# 01_-_MC.net
KiCad netlist of a schematic drawn in Altium Designer
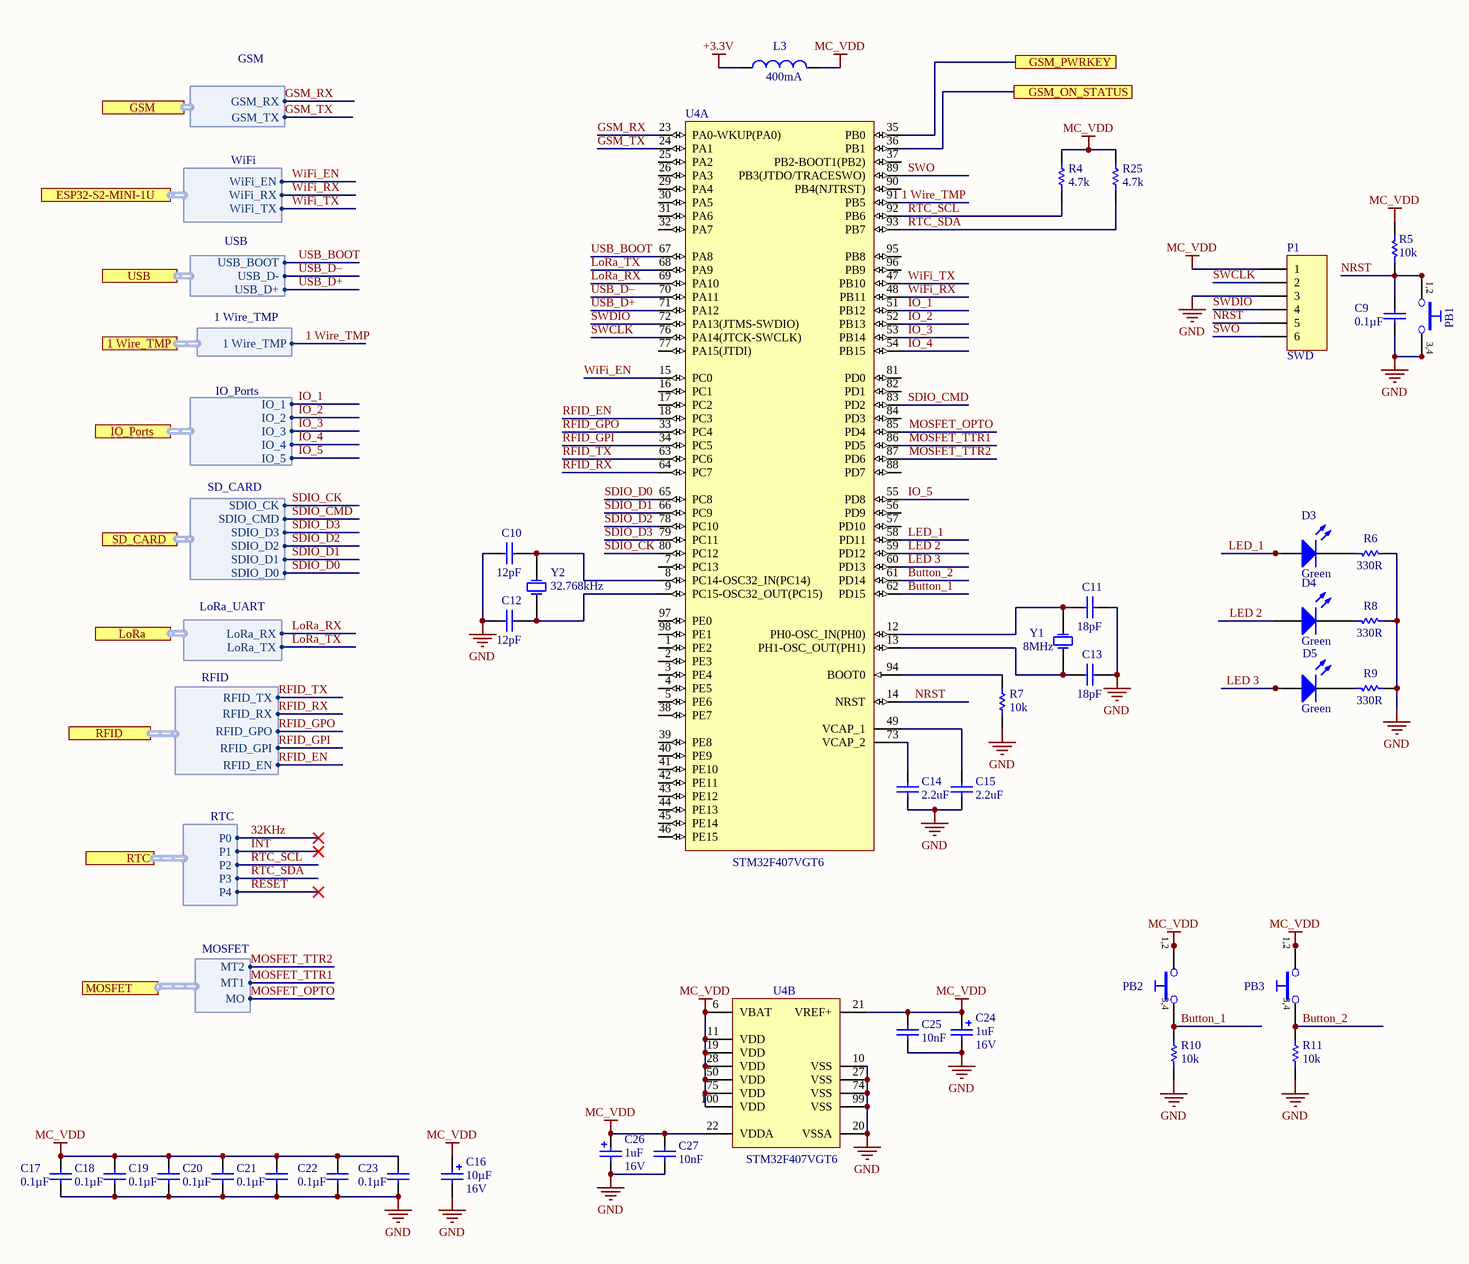
[diagram p0: [01] - MC.SchDoc]

(export (version "E")
  (design (tool "Eeschema 10.0.6"))
  (components
    (comp (ref "C9")
      (value "Capacitor")
      (footprint "Cap 0603")
      (description "Chip Capacitor Nonpolar")
      (fields
        (field (name "MANUFACTURER") "Kemet")
        (field (name "MANUFACTURER PART NUMBER") "C0603C104K5RACTU")
        (field (name "CAPACITANCE") "0.1µF")
      )
      (libsource (lib "Altium_Library") (part "Capacitor"))
    )
    (comp (ref "C10")
      (value "Capacitor")
      (footprint "Cap 0603")
      (description "Chip Capacitor Nonpolar")
      (fields
        (field (name "MANUFACTURER") "KEMET")
        (field (name "MANUFACTURER PART NUMBER") "C0603C120J5GAC-TU")
        (field (name "CAPACITANCE") "12pF")
      )
      (libsource (lib "Altium_Library") (part "Capacitor"))
    )
    (comp (ref "C11")
      (value "Capacitor")
      (footprint "Cap 0603")
      (description "Chip Capacitor Nonpolar")
      (fields
        (field (name "MANUFACTURER") "KEMET")
        (field (name "MANUFACTURER PART NUMBER") "C0603C180K5GACTU")
        (field (name "CAPACITANCE") "18pF")
      )
      (libsource (lib "Altium_Library") (part "Capacitor"))
    )
    (comp (ref "C12")
      (value "Capacitor")
      (footprint "Cap 0603")
      (description "Chip Capacitor Nonpolar")
      (fields
        (field (name "MANUFACTURER") "KEMET")
        (field (name "MANUFACTURER PART NUMBER") "C0603C120J5GAC-TU")
        (field (name "CAPACITANCE") "12pF")
      )
      (libsource (lib "Altium_Library") (part "Capacitor"))
    )
    (comp (ref "C13")
      (value "Capacitor")
      (footprint "Cap 0603")
      (description "Chip Capacitor Nonpolar")
      (fields
        (field (name "MANUFACTURER") "KEMET")
        (field (name "MANUFACTURER PART NUMBER") "C0603C180K5GACTU")
        (field (name "CAPACITANCE") "18pF")
      )
      (libsource (lib "Altium_Library") (part "Capacitor"))
    )
    (comp (ref "C14")
      (value "Capacitor")
      (footprint "Cap 0603")
      (description "Chip Capacitor Nonpolar")
      (fields
        (field (name "MANUFACTURER") "Samsung")
        (field (name "MANUFACTURER PART NUMBER") "CL21A225KAFNNNG")
        (field (name "CAPACITANCE") "2.2uF")
      )
      (libsource (lib "Altium_Library") (part "Capacitor"))
    )
    (comp (ref "C15")
      (value "Capacitor")
      (footprint "Cap 0603")
      (description "Chip Capacitor Nonpolar")
      (fields
        (field (name "MANUFACTURER") "Samsung")
        (field (name "MANUFACTURER PART NUMBER") "CL21A225KAFNNNG")
        (field (name "CAPACITANCE") "2.2uF")
      )
      (libsource (lib "Altium_Library") (part "Capacitor"))
    )
    (comp (ref "C16")
      (value "Capacitor Polarized")
      (footprint "Tantalum 3216 A")
      (description "Tantalum Capacitor")
      (fields
        (field (name "MANUFACTURER") "Kemet")
        (field (name "MANUFACTURER PART NUMBER") "T491A106K016AT")
        (field (name "CAPACITANCE") "10µF")
        (field (name "VOLTAGE - RATED") "16V")
      )
      (libsource (lib "Altium_Library") (part "Capacitor Polarized"))
    )
    (comp (ref "C17")
      (value "Capacitor")
      (footprint "Cap 0603")
      (description "Chip Capacitor Nonpolar")
      (fields
        (field (name "MANUFACTURER") "Kemet")
        (field (name "MANUFACTURER PART NUMBER") "C0603C104K5RACTU")
        (field (name "CAPACITANCE") "0.1µF")
      )
      (libsource (lib "Altium_Library") (part "Capacitor"))
    )
    (comp (ref "C18")
      (value "Capacitor")
      (footprint "Cap 0603")
      (description "Chip Capacitor Nonpolar")
      (fields
        (field (name "MANUFACTURER") "Kemet")
        (field (name "MANUFACTURER PART NUMBER") "C0603C104K5RACTU")
        (field (name "CAPACITANCE") "0.1µF")
      )
      (libsource (lib "Altium_Library") (part "Capacitor"))
    )
    (comp (ref "C19")
      (value "Capacitor")
      (footprint "Cap 0603")
      (description "Chip Capacitor Nonpolar")
      (fields
        (field (name "MANUFACTURER") "Kemet")
        (field (name "MANUFACTURER PART NUMBER") "C0603C104K5RACTU")
        (field (name "CAPACITANCE") "0.1µF")
      )
      (libsource (lib "Altium_Library") (part "Capacitor"))
    )
    (comp (ref "C20")
      (value "Capacitor")
      (footprint "Cap 0603")
      (description "Chip Capacitor Nonpolar")
      (fields
        (field (name "MANUFACTURER") "Kemet")
        (field (name "MANUFACTURER PART NUMBER") "C0603C104K5RACTU")
        (field (name "CAPACITANCE") "0.1µF")
      )
      (libsource (lib "Altium_Library") (part "Capacitor"))
    )
    (comp (ref "C21")
      (value "Capacitor")
      (footprint "Cap 0603")
      (description "Chip Capacitor Nonpolar")
      (fields
        (field (name "MANUFACTURER") "Kemet")
        (field (name "MANUFACTURER PART NUMBER") "C0603C104K5RACTU")
        (field (name "CAPACITANCE") "0.1µF")
      )
      (libsource (lib "Altium_Library") (part "Capacitor"))
    )
    (comp (ref "C22")
      (value "Capacitor")
      (footprint "Cap 0603")
      (description "Chip Capacitor Nonpolar")
      (fields
        (field (name "MANUFACTURER") "Kemet")
        (field (name "MANUFACTURER PART NUMBER") "C0603C104K5RACTU")
        (field (name "CAPACITANCE") "0.1µF")
      )
      (libsource (lib "Altium_Library") (part "Capacitor"))
    )
    (comp (ref "C23")
      (value "Capacitor")
      (footprint "Cap 0603")
      (description "Chip Capacitor Nonpolar")
      (fields
        (field (name "MANUFACTURER") "Kemet")
        (field (name "MANUFACTURER PART NUMBER") "C0603C104K5RACTU")
        (field (name "CAPACITANCE") "0.1µF")
      )
      (libsource (lib "Altium_Library") (part "Capacitor"))
    )
    (comp (ref "C24")
      (value "Capacitor Polarized")
      (footprint "Tantalum 3216 A")
      (description "Tantalum Capacitor")
      (fields
        (field (name "MANUFACTURER") "Vishay Sprague")
        (field (name "MANUFACTURER PART NUMBER") "293D105X9016A2TE3")
        (field (name "CAPACITANCE") "1uF")
        (field (name "VOLTAGE RATING") "16V")
      )
      (libsource (lib "Altium_Library") (part "Capacitor Polarized"))
    )
    (comp (ref "C25")
      (value "Capacitor")
      (footprint "Cap 0603")
      (description "Chip Capacitor Nonpolar")
      (fields
        (field (name "MANUFACTURER") "Samsung")
        (field (name "MANUFACTURER PART NUMBER") "CL10B103KB8WPNC")
        (field (name "CAPACITANCE") "10nF")
      )
      (libsource (lib "Altium_Library") (part "Capacitor"))
    )
    (comp (ref "C26")
      (value "Capacitor Polarized")
      (footprint "Tantalum 3216 A")
      (description "Tantalum Capacitor")
      (fields
        (field (name "MANUFACTURER") "Vishay Sprague")
        (field (name "MANUFACTURER PART NUMBER") "293D105X9016A2TE3")
        (field (name "CAPACITANCE") "1uF")
        (field (name "VOLTAGE RATING") "16V")
      )
      (libsource (lib "Altium_Library") (part "Capacitor Polarized"))
    )
    (comp (ref "C27")
      (value "Capacitor")
      (footprint "Cap 0603")
      (description "Chip Capacitor Nonpolar")
      (fields
        (field (name "MANUFACTURER") "Samsung")
        (field (name "MANUFACTURER PART NUMBER") "CL10B103KB8WPNC")
        (field (name "CAPACITANCE") "10nF")
      )
      (libsource (lib "Altium_Library") (part "Capacitor"))
    )
    (comp (ref "D3")
      (value "LED")
      (footprint "Led 0805 green")
      (description "Led 0805")
      (fields
        (field (name "MANUFACTURER") "Vishay Lite-On")
        (field (name "MANUFACTURER PART NUMBER") "LTST-S220GKT")
        (field (name "COLOUR") "Green")
      )
      (libsource (lib "Altium_Library") (part "LED"))
    )
    (comp (ref "D4")
      (value "LED")
      (footprint "Led 0805 green")
      (description "Led 0805")
      (fields
        (field (name "MANUFACTURER") "Vishay Lite-On")
        (field (name "MANUFACTURER PART NUMBER") "LTST-S220GKT")
        (field (name "COLOUR") "Green")
      )
      (libsource (lib "Altium_Library") (part "LED"))
    )
    (comp (ref "D5")
      (value "LED")
      (footprint "Led 0805 green")
      (description "Led 0805")
      (fields
        (field (name "MANUFACTURER") "Vishay Lite-On")
        (field (name "MANUFACTURER PART NUMBER") "LTST-S220GKT")
        (field (name "COLOUR") "Green")
      )
      (libsource (lib "Altium_Library") (part "LED"))
    )
    (comp (ref "L3")
      (value "Inductor")
      (footprint "0603")
      (description "Sumida inductore ferrite core smd")
      (fields
        (field (name "MANUFACTURER") "Murata Electronics North America")
        (field (name "MANUFACTURER PART NUMBER") "BLM18AG102SN1D")
        (field (name "CURRENT RATING (MAX)") "400mA")
      )
      (libsource (lib "Altium_Library") (part "Inductor"))
    )
    (comp (ref "P1")
      (value "SWD")
      (footprint "HDR1X6")
      (description "Header, 6-Pin")
      (fields (field (name "PUBLISHER") "Altium Limited"))
      (libsource (lib "Miscellaneous Connectors") (part "Header 6"))
    )
    (comp (ref "PB1")
      (value "Push Button")
      (footprint "PB_OMRON_B3F-1000")
      (description "Push-Button Switch SPDT")
      (fields
        (field (name "PART NUMBER") "PB_OMRON_B3F-1000")
        (field (name "MANUFACTURER") "OMRON")
        (field (name "AUTHOR") "CERN DEM JMW")
      )
      (libsource (lib "") (part "PB SPST 12NO-34NO_1"))
    )
    (comp (ref "PB2")
      (value "Push Button")
      (footprint "PB_OMRON_B3F-1000")
      (description "Push-Button Switch SPDT")
      (fields
        (field (name "PART NUMBER") "PB_OMRON_B3F-1000")
        (field (name "MANUFACTURER") "OMRON")
        (field (name "AUTHOR") "CERN DEM JMW")
      )
      (libsource (lib "Eletro-mechanical") (part "PB SPST 12NO-34NO"))
    )
    (comp (ref "PB3")
      (value "Push Button")
      (footprint "PB_OMRON_B3F-1000")
      (description "Push-Button Switch SPDT")
      (fields
        (field (name "PART NUMBER") "PB_OMRON_B3F-1000")
        (field (name "MANUFACTURER") "OMRON")
        (field (name "AUTHOR") "CERN DEM JMW")
      )
      (libsource (lib "Eletro-mechanical") (part "PB SPST 12NO-34NO"))
    )
    (comp (ref "R4")
      (value "Res1")
      (footprint "Res-0603")
      (description "Chip Resistor")
      (fields
        (field (name "MANUFACTURER") "Panasonic")
        (field (name "MANUFACTURER PART NUMBER") "ERJ-3GEYJ222V")
        (field (name "RESISTANCE") "4.7k")
      )
      (libsource (lib "Altium_Library") (part "Res1"))
    )
    (comp (ref "R5")
      (value "Res1")
      (footprint "Res-0603")
      (description "Chip Resistor")
      (fields
        (field (name "MANUFACTURER") "Panasonic")
        (field (name "MANUFACTURER PART NUMBER") "ERJ-3GEYJ103V")
        (field (name "RESISTANCE") "10k")
      )
      (libsource (lib "Altium_Library") (part "Res1"))
    )
    (comp (ref "R6")
      (value "Res1")
      (footprint "Res-0603")
      (description "Chip Resistor")
      (fields
        (field (name "MANUFACTURER") "Panasonic")
        (field (name "MANUFACTURER PART NUMBER") "ERJ-3EKF3300V")
        (field (name "RESISTANCE") "330R")
      )
      (libsource (lib "Altium_Library") (part "Res1"))
    )
    (comp (ref "R7")
      (value "Res1")
      (footprint "Res-0603")
      (description "Chip Resistor")
      (fields
        (field (name "MANUFACTURER") "Panasonic")
        (field (name "MANUFACTURER PART NUMBER") "ERJ-3GEYJ103V")
        (field (name "RESISTANCE") "10k")
      )
      (libsource (lib "Altium_Library") (part "Res1"))
    )
    (comp (ref "R8")
      (value "Res1")
      (footprint "Res-0603")
      (description "Chip Resistor")
      (fields
        (field (name "MANUFACTURER") "Panasonic")
        (field (name "MANUFACTURER PART NUMBER") "ERJ-3EKF3300V")
        (field (name "RESISTANCE") "330R")
      )
      (libsource (lib "Altium_Library") (part "Res1"))
    )
    (comp (ref "R9")
      (value "Res1")
      (footprint "Res-0603")
      (description "Chip Resistor")
      (fields
        (field (name "MANUFACTURER") "Panasonic")
        (field (name "MANUFACTURER PART NUMBER") "ERJ-3EKF3300V")
        (field (name "RESISTANCE") "330R")
      )
      (libsource (lib "Altium_Library") (part "Res1"))
    )
    (comp (ref "R10")
      (value "Res1")
      (footprint "Res-0603")
      (description "Chip Resistor")
      (fields
        (field (name "MANUFACTURER") "Panasonic")
        (field (name "MANUFACTURER PART NUMBER") "ERJ-3GEYJ103V")
        (field (name "RESISTANCE") "10k")
      )
      (libsource (lib "Altium_Library") (part "Res1"))
    )
    (comp (ref "R11")
      (value "Res1")
      (footprint "Res-0603")
      (description "Chip Resistor")
      (fields
        (field (name "MANUFACTURER") "Panasonic")
        (field (name "MANUFACTURER PART NUMBER") "ERJ-3GEYJ103V")
        (field (name "RESISTANCE") "10k")
      )
      (libsource (lib "Altium_Library") (part "Res1"))
    )
    (comp (ref "R25")
      (value "Res1")
      (footprint "Res-0603")
      (description "Chip Resistor")
      (fields
        (field (name "MANUFACTURER") "Panasonic")
        (field (name "MANUFACTURER PART NUMBER") "ERJ-3GEYJ222V")
        (field (name "RESISTANCE") "4.7k")
      )
      (libsource (lib "Altium_Library") (part "Res1"))
    )
    (comp (ref "U4")
      (value "STM32F407VGT6J")
      (footprint "LQFP100_N")
      (fields
        (field (name "MANUFACTURER") "STMicroelectronics")
        (field (name "MANUFACTURER PART NUMBER") "STM32F407VGT6")
      )
      (libsource (lib "STMicroelectronics STM32 F4") (part "STM32F407VGT6J"))
    )
    (comp (ref "Y1")
      (value "XTAL2pin")
      (footprint "ABM3")
      (description "Crystal Oscillator")
      (fields
        (field (name "MANUFACTURER") "Abracon Corporation")
        (field (name "MANUFACTURER PART NUMBER") "ABM3-8.000MHZ-D2Y-T")
        (field (name "FREQUENCY") "8MHz")
        (field (name "PUBLISHER") "Ruslan Gimazetdinov")
      )
      (libsource (lib "Altium_Library") (part "XTAL2pin"))
    )
    (comp (ref "Y2")
      (value "32768")
      (footprint "ABM3")
      (description "Crystal Oscillator")
      (fields
        (field (name "MANUFACTURER") "ECS International")
        (field (name "MANUFACTURER PART NUMBER") "ECS-.327-12.5-34B-TR")
        (field (name "FREQUENCY") "32.768kHz")
      )
      (libsource (lib "Altium_Library") (part "XTAL2pin"))
    )
  )
  (nets
    (net (code "12") (name "+3.3V") (class "Default")
      (node (ref "L3") (pin "1") (pinfunction "1_1") (pintype "passive"))
    )
    (net (code "13") (name "/1 Wire_TMP") (class "Default")
      (node (ref "U4") (pin "91") (pinfunction "PB5_91") (pintype "bidirectional"))
    )
    (net (code "15") (name "/Button_1") (class "Default")
      (node (ref "PB2") (pin "3") (pinfunction "3_3") (pintype "passive"))
      (node (ref "PB2") (pin "4") (pinfunction "4_4") (pintype "passive"))
      (node (ref "R10") (pin "2") (pinfunction "2_2") (pintype "passive"))
      (node (ref "U4") (pin "62") (pinfunction "PD15_62") (pintype "bidirectional"))
    )
    (net (code "16") (name "/Button_2") (class "Default")
      (node (ref "PB3") (pin "3") (pinfunction "3_3") (pintype "passive"))
      (node (ref "PB3") (pin "4") (pinfunction "4_4") (pintype "passive"))
      (node (ref "R11") (pin "2") (pinfunction "2_2") (pintype "passive"))
      (node (ref "U4") (pin "61") (pinfunction "PD14_61") (pintype "bidirectional"))
    )
    (net (code "17") (name "/GSM_ON_STATUS") (class "Default")
      (node (ref "U4") (pin "36") (pinfunction "PB1_36") (pintype "bidirectional"))
    )
    (net (code "18") (name "/GSM_PWRKEY") (class "Default")
      (node (ref "U4") (pin "35") (pinfunction "PB0_35") (pintype "bidirectional"))
    )
    (net (code "19") (name "/GSM_RX") (class "Default")
      (node (ref "U4") (pin "23") (pinfunction "PA0-WKUP(PA0)_23") (pintype "bidirectional"))
    )
    (net (code "20") (name "/GSM_TX") (class "Default")
      (node (ref "U4") (pin "24") (pinfunction "PA1_24") (pintype "bidirectional"))
    )
    (net (code "21") (name "/IO_1") (class "Default")
      (node (ref "U4") (pin "51") (pinfunction "PB12_51") (pintype "bidirectional"))
    )
    (net (code "22") (name "/IO_2") (class "Default")
      (node (ref "U4") (pin "52") (pinfunction "PB13_52") (pintype "bidirectional"))
    )
    (net (code "23") (name "/IO_3") (class "Default")
      (node (ref "U4") (pin "53") (pinfunction "PB14_53") (pintype "bidirectional"))
    )
    (net (code "24") (name "/IO_4") (class "Default")
      (node (ref "U4") (pin "54") (pinfunction "PB15_54") (pintype "bidirectional"))
    )
    (net (code "25") (name "/IO_5") (class "Default")
      (node (ref "U4") (pin "55") (pinfunction "PD8_55") (pintype "bidirectional"))
    )
    (net (code "26") (name "/LED 2") (class "Default")
      (node (ref "D4") (pin "1") (pinfunction "A_1") (pintype "passive"))
      (node (ref "U4") (pin "59") (pinfunction "PD12_59") (pintype "bidirectional"))
    )
    (net (code "27") (name "/LED 3") (class "Default")
      (node (ref "D5") (pin "1") (pinfunction "A_1") (pintype "passive"))
      (node (ref "U4") (pin "60") (pinfunction "PD13_60") (pintype "bidirectional"))
    )
    (net (code "28") (name "/LED_1") (class "Default")
      (node (ref "D3") (pin "1") (pinfunction "A_1") (pintype "passive"))
      (node (ref "U4") (pin "58") (pinfunction "PD11_58") (pintype "bidirectional"))
    )
    (net (code "29") (name "/LoRa_RX") (class "Default")
      (node (ref "U4") (pin "69") (pinfunction "PA10_69") (pintype "bidirectional"))
    )
    (net (code "30") (name "/LoRa_TX") (class "Default")
      (node (ref "U4") (pin "68") (pinfunction "PA9_68") (pintype "bidirectional"))
    )
    (net (code "31") (name "/MOSFET_OPTO") (class "Default")
      (node (ref "U4") (pin "85") (pinfunction "PD4_85") (pintype "bidirectional"))
    )
    (net (code "32") (name "/MOSFET_TTR1") (class "Default")
      (node (ref "U4") (pin "86") (pinfunction "PD5_86") (pintype "bidirectional"))
    )
    (net (code "33") (name "/MOSFET_TTR2") (class "Default")
      (node (ref "U4") (pin "87") (pinfunction "PD6_87") (pintype "bidirectional"))
    )
    (net (code "34") (name "/NRST") (class "Default")
      (node (ref "C9") (pin "2") (pinfunction "2_2") (pintype "passive"))
      (node (ref "P1") (pin "5") (pinfunction "5_5") (pintype "passive"))
      (node (ref "PB1") (pin "1") (pinfunction "1_1") (pintype "passive"))
      (node (ref "PB1") (pin "2") (pinfunction "2_2") (pintype "passive"))
      (node (ref "R5") (pin "1") (pinfunction "1_1") (pintype "passive"))
      (node (ref "U4") (pin "14") (pinfunction "NRST_14") (pintype "bidirectional"))
    )
    (net (code "36") (name "/RFID_EN") (class "Default")
      (node (ref "U4") (pin "18") (pinfunction "PC3_18") (pintype "bidirectional"))
    )
    (net (code "37") (name "/RFID_GPI") (class "Default")
      (node (ref "U4") (pin "34") (pinfunction "PC5_34") (pintype "bidirectional"))
    )
    (net (code "38") (name "/RFID_GPO") (class "Default")
      (node (ref "U4") (pin "33") (pinfunction "PC4_33") (pintype "bidirectional"))
    )
    (net (code "39") (name "/RFID_RX") (class "Default")
      (node (ref "U4") (pin "64") (pinfunction "PC7_64") (pintype "bidirectional"))
    )
    (net (code "40") (name "/RFID_TX") (class "Default")
      (node (ref "U4") (pin "63") (pinfunction "PC6_63") (pintype "bidirectional"))
    )
    (net (code "41") (name "/RTC_SCL") (class "Default")
      (node (ref "R4") (pin "2") (pinfunction "2_2") (pintype "passive"))
      (node (ref "U4") (pin "92") (pinfunction "PB6_92") (pintype "bidirectional"))
    )
    (net (code "42") (name "/RTC_SDA") (class "Default")
      (node (ref "R25") (pin "2") (pinfunction "2_2") (pintype "passive"))
      (node (ref "U4") (pin "93") (pinfunction "PB7_93") (pintype "bidirectional"))
    )
    (net (code "43") (name "/SDIO_CK") (class "Default")
      (node (ref "U4") (pin "80") (pinfunction "PC12_80") (pintype "bidirectional"))
    )
    (net (code "44") (name "/SDIO_CMD") (class "Default")
      (node (ref "U4") (pin "83") (pinfunction "PD2_83") (pintype "bidirectional"))
    )
    (net (code "45") (name "/SDIO_D0") (class "Default")
      (node (ref "U4") (pin "65") (pinfunction "PC8_65") (pintype "bidirectional"))
    )
    (net (code "46") (name "/SDIO_D1") (class "Default")
      (node (ref "U4") (pin "66") (pinfunction "PC9_66") (pintype "bidirectional"))
    )
    (net (code "47") (name "/SDIO_D2") (class "Default")
      (node (ref "U4") (pin "78") (pinfunction "PC10_78") (pintype "bidirectional"))
    )
    (net (code "48") (name "/SDIO_D3") (class "Default")
      (node (ref "U4") (pin "79") (pinfunction "PC11_79") (pintype "bidirectional"))
    )
    (net (code "49") (name "/SWCLK") (class "Default")
      (node (ref "P1") (pin "2") (pinfunction "2_2") (pintype "passive"))
      (node (ref "U4") (pin "76") (pinfunction "PA14(JTCK-SWCLK)_76") (pintype "bidirectional"))
    )
    (net (code "50") (name "/SWDIO") (class "Default")
      (node (ref "P1") (pin "4") (pinfunction "4_4") (pintype "passive"))
      (node (ref "U4") (pin "72") (pinfunction "PA13(JTMS-SWDIO)_72") (pintype "bidirectional"))
    )
    (net (code "51") (name "/SWO") (class "Default")
      (node (ref "P1") (pin "6") (pinfunction "6_6") (pintype "passive"))
      (node (ref "U4") (pin "89") (pinfunction "PB3(JTDO/TRACESWO)_89") (pintype "bidirectional"))
    )
    (net (code "52") (name "/USB_BOOT") (class "Default")
      (node (ref "U4") (pin "67") (pinfunction "PA8_67") (pintype "bidirectional"))
    )
    (net (code "53") (name "/USB_D+") (class "Default")
      (node (ref "U4") (pin "71") (pinfunction "PA12_71") (pintype "bidirectional"))
    )
    (net (code "54") (name "/USB_D–") (class "Default")
      (node (ref "U4") (pin "70") (pinfunction "PA11_70") (pintype "bidirectional"))
    )
    (net (code "55") (name "/WiFi_EN") (class "Default")
      (node (ref "U4") (pin "15") (pinfunction "PC0_15") (pintype "bidirectional"))
    )
    (net (code "56") (name "/WiFi_RX") (class "Default")
      (node (ref "U4") (pin "48") (pinfunction "PB11_48") (pintype "bidirectional"))
    )
    (net (code "57") (name "/WiFi_TX") (class "Default")
      (node (ref "U4") (pin "47") (pinfunction "PB10_47") (pintype "bidirectional"))
    )
    (net (code "69") (name "GND") (class "Default")
      (node (ref "C10") (pin "2") (pinfunction "2_2") (pintype "passive"))
      (node (ref "C11") (pin "2") (pinfunction "2_2") (pintype "passive"))
      (node (ref "C12") (pin "2") (pinfunction "2_2") (pintype "passive"))
      (node (ref "C13") (pin "2") (pinfunction "2_2") (pintype "passive"))
      (node (ref "C14") (pin "1") (pinfunction "1_1") (pintype "passive"))
      (node (ref "C15") (pin "1") (pinfunction "1_1") (pintype "passive"))
      (node (ref "C16") (pin "2") (pinfunction "2_2") (pintype "passive"))
      (node (ref "C17") (pin "1") (pinfunction "1_1") (pintype "passive"))
      (node (ref "C18") (pin "1") (pinfunction "1_1") (pintype "passive"))
      (node (ref "C19") (pin "1") (pinfunction "1_1") (pintype "passive"))
      (node (ref "C20") (pin "1") (pinfunction "1_1") (pintype "passive"))
      (node (ref "C21") (pin "1") (pinfunction "1_1") (pintype "passive"))
      (node (ref "C22") (pin "1") (pinfunction "1_1") (pintype "passive"))
      (node (ref "C23") (pin "1") (pinfunction "1_1") (pintype "passive"))
      (node (ref "C24") (pin "2") (pinfunction "2_2") (pintype "passive"))
      (node (ref "C25") (pin "1") (pinfunction "1_1") (pintype "passive"))
      (node (ref "C26") (pin "2") (pinfunction "2_2") (pintype "passive"))
      (node (ref "C27") (pin "1") (pinfunction "1_1") (pintype "passive"))
      (node (ref "C9") (pin "1") (pinfunction "1_1") (pintype "passive"))
      (node (ref "P1") (pin "3") (pinfunction "3_3") (pintype "passive"))
      (node (ref "PB1") (pin "3") (pinfunction "3_3") (pintype "passive"))
      (node (ref "PB1") (pin "4") (pinfunction "4_4") (pintype "passive"))
      (node (ref "R10") (pin "1") (pinfunction "1_1") (pintype "passive"))
      (node (ref "R11") (pin "1") (pinfunction "1_1") (pintype "passive"))
      (node (ref "R6") (pin "2") (pinfunction "2_2") (pintype "passive"))
      (node (ref "R7") (pin "1") (pinfunction "1_1") (pintype "passive"))
      (node (ref "R8") (pin "2") (pinfunction "2_2") (pintype "passive"))
      (node (ref "R9") (pin "2") (pinfunction "2_2") (pintype "passive"))
      (node (ref "U4") (pin "10") (pinfunction "VSS_10") (pintype "power_in"))
      (node (ref "U4") (pin "20") (pinfunction "VSSA_20") (pintype "power_in"))
      (node (ref "U4") (pin "27") (pinfunction "VSS_27") (pintype "power_in"))
      (node (ref "U4") (pin "74") (pinfunction "VSS_74") (pintype "power_in"))
      (node (ref "U4") (pin "99") (pinfunction "VSS_99") (pintype "power_in"))
    )
    (net (code "70") (name "MC_VDD") (class "Default")
      (node (ref "C16") (pin "1") (pinfunction "1_1") (pintype "passive"))
      (node (ref "C17") (pin "2") (pinfunction "2_2") (pintype "passive"))
      (node (ref "C18") (pin "2") (pinfunction "2_2") (pintype "passive"))
      (node (ref "C19") (pin "2") (pinfunction "2_2") (pintype "passive"))
      (node (ref "C20") (pin "2") (pinfunction "2_2") (pintype "passive"))
      (node (ref "C21") (pin "2") (pinfunction "2_2") (pintype "passive"))
      (node (ref "C22") (pin "2") (pinfunction "2_2") (pintype "passive"))
      (node (ref "C23") (pin "2") (pinfunction "2_2") (pintype "passive"))
      (node (ref "C24") (pin "1") (pinfunction "1_1") (pintype "passive"))
      (node (ref "C25") (pin "2") (pinfunction "2_2") (pintype "passive"))
      (node (ref "C26") (pin "1") (pinfunction "1_1") (pintype "passive"))
      (node (ref "C27") (pin "2") (pinfunction "2_2") (pintype "passive"))
      (node (ref "L3") (pin "2") (pinfunction "2_2") (pintype "passive"))
      (node (ref "P1") (pin "1") (pinfunction "1_1") (pintype "passive"))
      (node (ref "PB2") (pin "1") (pinfunction "1_1") (pintype "passive"))
      (node (ref "PB2") (pin "2") (pinfunction "2_2") (pintype "passive"))
      (node (ref "PB3") (pin "1") (pinfunction "1_1") (pintype "passive"))
      (node (ref "PB3") (pin "2") (pinfunction "2_2") (pintype "passive"))
      (node (ref "R25") (pin "1") (pinfunction "1_1") (pintype "passive"))
      (node (ref "R4") (pin "1") (pinfunction "1_1") (pintype "passive"))
      (node (ref "R5") (pin "2") (pinfunction "2_2") (pintype "passive"))
      (node (ref "U4") (pin "100") (pinfunction "VDD_100") (pintype "power_in"))
      (node (ref "U4") (pin "11") (pinfunction "VDD_11") (pintype "power_in"))
      (node (ref "U4") (pin "19") (pinfunction "VDD_19") (pintype "power_in"))
      (node (ref "U4") (pin "21") (pinfunction "VREF+_21") (pintype "power_in"))
      (node (ref "U4") (pin "22") (pinfunction "VDDA_22") (pintype "power_in"))
      (node (ref "U4") (pin "28") (pinfunction "VDD_28") (pintype "power_in"))
      (node (ref "U4") (pin "50") (pinfunction "VDD_50") (pintype "power_in"))
      (node (ref "U4") (pin "6") (pinfunction "VBAT_6") (pintype "power_in"))
      (node (ref "U4") (pin "75") (pinfunction "VDD_75") (pintype "power_in"))
    )
    (net (code "71") (name "Net-(D3-K)") (class "Default")
      (node (ref "D3") (pin "2") (pinfunction "K_2") (pintype "passive"))
      (node (ref "R6") (pin "1") (pinfunction "1_1") (pintype "passive"))
    )
    (net (code "72") (name "Net-(D4-K)") (class "Default")
      (node (ref "D4") (pin "2") (pinfunction "K_2") (pintype "passive"))
      (node (ref "R8") (pin "1") (pinfunction "1_1") (pintype "passive"))
    )
    (net (code "73") (name "Net-(D5-K)") (class "Default")
      (node (ref "D5") (pin "2") (pinfunction "K_2") (pintype "passive"))
      (node (ref "R9") (pin "1") (pinfunction "1_1") (pintype "passive"))
    )
    (net (code "74") (name "Net-(U4A-BOOT0)") (class "Default")
      (node (ref "R7") (pin "2") (pinfunction "2_2") (pintype "passive"))
      (node (ref "U4") (pin "94") (pinfunction "BOOT0_94") (pintype "input"))
    )
    (net (code "75") (name "Net-(U4A-PC14-OSC32_IN(PC14))") (class "Default")
      (node (ref "C10") (pin "1") (pinfunction "1_1") (pintype "passive"))
      (node (ref "U4") (pin "8") (pinfunction "PC14-OSC32_IN(PC14)_8") (pintype "bidirectional"))
      (node (ref "Y2") (pin "1") (pinfunction "OSC1_1") (pintype "passive"))
    )
    (net (code "76") (name "Net-(U4A-PC15-OSC32_OUT(PC15))") (class "Default")
      (node (ref "C12") (pin "1") (pinfunction "1_1") (pintype "passive"))
      (node (ref "U4") (pin "9") (pinfunction "PC15-OSC32_OUT(PC15)_9") (pintype "bidirectional"))
      (node (ref "Y2") (pin "2") (pinfunction "OSC2_2") (pintype "passive"))
    )
    (net (code "77") (name "Net-(U4A-PH0-OSC_IN(PH0))") (class "Default")
      (node (ref "C11") (pin "1") (pinfunction "1_1") (pintype "passive"))
      (node (ref "U4") (pin "12") (pinfunction "PH0-OSC_IN(PH0)_12") (pintype "bidirectional"))
      (node (ref "Y1") (pin "2") (pinfunction "OSC2_2") (pintype "passive"))
    )
    (net (code "78") (name "Net-(U4A-PH1-OSC_OUT(PH1))") (class "Default")
      (node (ref "C13") (pin "1") (pinfunction "1_1") (pintype "passive"))
      (node (ref "U4") (pin "13") (pinfunction "PH1-OSC_OUT(PH1)_13") (pintype "bidirectional"))
      (node (ref "Y1") (pin "1") (pinfunction "OSC1_1") (pintype "passive"))
    )
    (net (code "79") (name "Net-(U4A-VCAP_1)") (class "Default")
      (node (ref "C15") (pin "2") (pinfunction "2_2") (pintype "passive"))
      (node (ref "U4") (pin "49") (pinfunction "VCAP_1_49") (pintype "power_in"))
    )
    (net (code "80") (name "Net-(U4A-VCAP_2)") (class "Default")
      (node (ref "C14") (pin "2") (pinfunction "2_2") (pintype "passive"))
      (node (ref "U4") (pin "73") (pinfunction "VCAP_2_73") (pintype "power_in"))
    )
    (net (code "81") (name "unconnected-(U4A-PA2-Pad25)") (class "Default")
      (node (ref "U4") (pin "25") (pinfunction "PA2_25") (pintype "bidirectional"))
    )
    (net (code "82") (name "unconnected-(U4A-PA3-Pad26)") (class "Default")
      (node (ref "U4") (pin "26") (pinfunction "PA3_26") (pintype "bidirectional"))
    )
    (net (code "83") (name "unconnected-(U4A-PA4-Pad29)") (class "Default")
      (node (ref "U4") (pin "29") (pinfunction "PA4_29") (pintype "bidirectional"))
    )
    (net (code "84") (name "unconnected-(U4A-PA5-Pad30)") (class "Default")
      (node (ref "U4") (pin "30") (pinfunction "PA5_30") (pintype "bidirectional"))
    )
    (net (code "85") (name "unconnected-(U4A-PA6-Pad31)") (class "Default")
      (node (ref "U4") (pin "31") (pinfunction "PA6_31") (pintype "bidirectional"))
    )
    (net (code "86") (name "unconnected-(U4A-PA7-Pad32)") (class "Default")
      (node (ref "U4") (pin "32") (pinfunction "PA7_32") (pintype "bidirectional"))
    )
    (net (code "87") (name "unconnected-(U4A-PA15(JTDI)-Pad77)") (class "Default")
      (node (ref "U4") (pin "77") (pinfunction "PA15(JTDI)_77") (pintype "bidirectional"))
    )
    (net (code "88") (name "unconnected-(U4A-PB2-BOOT1(PB2)-Pad37)") (class "Default")
      (node (ref "U4") (pin "37") (pinfunction "PB2-BOOT1(PB2)_37") (pintype "bidirectional"))
    )
    (net (code "89") (name "unconnected-(U4A-PB4(NJTRST)-Pad90)") (class "Default")
      (node (ref "U4") (pin "90") (pinfunction "PB4(NJTRST)_90") (pintype "bidirectional"))
    )
    (net (code "90") (name "unconnected-(U4A-PB8-Pad95)") (class "Default")
      (node (ref "U4") (pin "95") (pinfunction "PB8_95") (pintype "bidirectional"))
    )
    (net (code "91") (name "unconnected-(U4A-PB9-Pad96)") (class "Default")
      (node (ref "U4") (pin "96") (pinfunction "PB9_96") (pintype "bidirectional"))
    )
    (net (code "92") (name "unconnected-(U4A-PC1-Pad16)") (class "Default")
      (node (ref "U4") (pin "16") (pinfunction "PC1_16") (pintype "bidirectional"))
    )
    (net (code "93") (name "unconnected-(U4A-PC2-Pad17)") (class "Default")
      (node (ref "U4") (pin "17") (pinfunction "PC2_17") (pintype "bidirectional"))
    )
    (net (code "94") (name "unconnected-(U4A-PC13-Pad7)") (class "Default")
      (node (ref "U4") (pin "7") (pinfunction "PC13_7") (pintype "bidirectional"))
    )
    (net (code "95") (name "unconnected-(U4A-PD0-Pad81)") (class "Default")
      (node (ref "U4") (pin "81") (pinfunction "PD0_81") (pintype "bidirectional"))
    )
    (net (code "96") (name "unconnected-(U4A-PD1-Pad82)") (class "Default")
      (node (ref "U4") (pin "82") (pinfunction "PD1_82") (pintype "bidirectional"))
    )
    (net (code "97") (name "unconnected-(U4A-PD3-Pad84)") (class "Default")
      (node (ref "U4") (pin "84") (pinfunction "PD3_84") (pintype "bidirectional"))
    )
    (net (code "98") (name "unconnected-(U4A-PD7-Pad88)") (class "Default")
      (node (ref "U4") (pin "88") (pinfunction "PD7_88") (pintype "bidirectional"))
    )
    (net (code "99") (name "unconnected-(U4A-PD9-Pad56)") (class "Default")
      (node (ref "U4") (pin "56") (pinfunction "PD9_56") (pintype "bidirectional"))
    )
    (net (code "100") (name "unconnected-(U4A-PD10-Pad57)") (class "Default")
      (node (ref "U4") (pin "57") (pinfunction "PD10_57") (pintype "bidirectional"))
    )
    (net (code "101") (name "unconnected-(U4A-PE0-Pad97)") (class "Default")
      (node (ref "U4") (pin "97") (pinfunction "PE0_97") (pintype "bidirectional"))
    )
    (net (code "102") (name "unconnected-(U4A-PE1-Pad98)") (class "Default")
      (node (ref "U4") (pin "98") (pinfunction "PE1_98") (pintype "bidirectional"))
    )
    (net (code "103") (name "unconnected-(U4A-PE2-Pad1)") (class "Default")
      (node (ref "U4") (pin "1") (pinfunction "PE2_1") (pintype "bidirectional"))
    )
    (net (code "104") (name "unconnected-(U4A-PE3-Pad2)") (class "Default")
      (node (ref "U4") (pin "2") (pinfunction "PE3_2") (pintype "bidirectional"))
    )
    (net (code "105") (name "unconnected-(U4A-PE4-Pad3)") (class "Default")
      (node (ref "U4") (pin "3") (pinfunction "PE4_3") (pintype "bidirectional"))
    )
    (net (code "106") (name "unconnected-(U4A-PE5-Pad4)") (class "Default")
      (node (ref "U4") (pin "4") (pinfunction "PE5_4") (pintype "bidirectional"))
    )
    (net (code "107") (name "unconnected-(U4A-PE6-Pad5)") (class "Default")
      (node (ref "U4") (pin "5") (pinfunction "PE6_5") (pintype "bidirectional"))
    )
    (net (code "108") (name "unconnected-(U4A-PE7-Pad38)") (class "Default")
      (node (ref "U4") (pin "38") (pinfunction "PE7_38") (pintype "bidirectional"))
    )
    (net (code "109") (name "unconnected-(U4A-PE8-Pad39)") (class "Default")
      (node (ref "U4") (pin "39") (pinfunction "PE8_39") (pintype "bidirectional"))
    )
    (net (code "110") (name "unconnected-(U4A-PE9-Pad40)") (class "Default")
      (node (ref "U4") (pin "40") (pinfunction "PE9_40") (pintype "bidirectional"))
    )
    (net (code "111") (name "unconnected-(U4A-PE10-Pad41)") (class "Default")
      (node (ref "U4") (pin "41") (pinfunction "PE10_41") (pintype "bidirectional"))
    )
    (net (code "112") (name "unconnected-(U4A-PE11-Pad42)") (class "Default")
      (node (ref "U4") (pin "42") (pinfunction "PE11_42") (pintype "bidirectional"))
    )
    (net (code "113") (name "unconnected-(U4A-PE12-Pad43)") (class "Default")
      (node (ref "U4") (pin "43") (pinfunction "PE12_43") (pintype "bidirectional"))
    )
    (net (code "114") (name "unconnected-(U4A-PE13-Pad44)") (class "Default")
      (node (ref "U4") (pin "44") (pinfunction "PE13_44") (pintype "bidirectional"))
    )
    (net (code "115") (name "unconnected-(U4A-PE14-Pad45)") (class "Default")
      (node (ref "U4") (pin "45") (pinfunction "PE14_45") (pintype "bidirectional"))
    )
    (net (code "116") (name "unconnected-(U4A-PE15-Pad46)") (class "Default")
      (node (ref "U4") (pin "46") (pinfunction "PE15_46") (pintype "bidirectional"))
    )
  )
)
